# panel.net
KiCad netlist of a schematic drawn in EAGLE
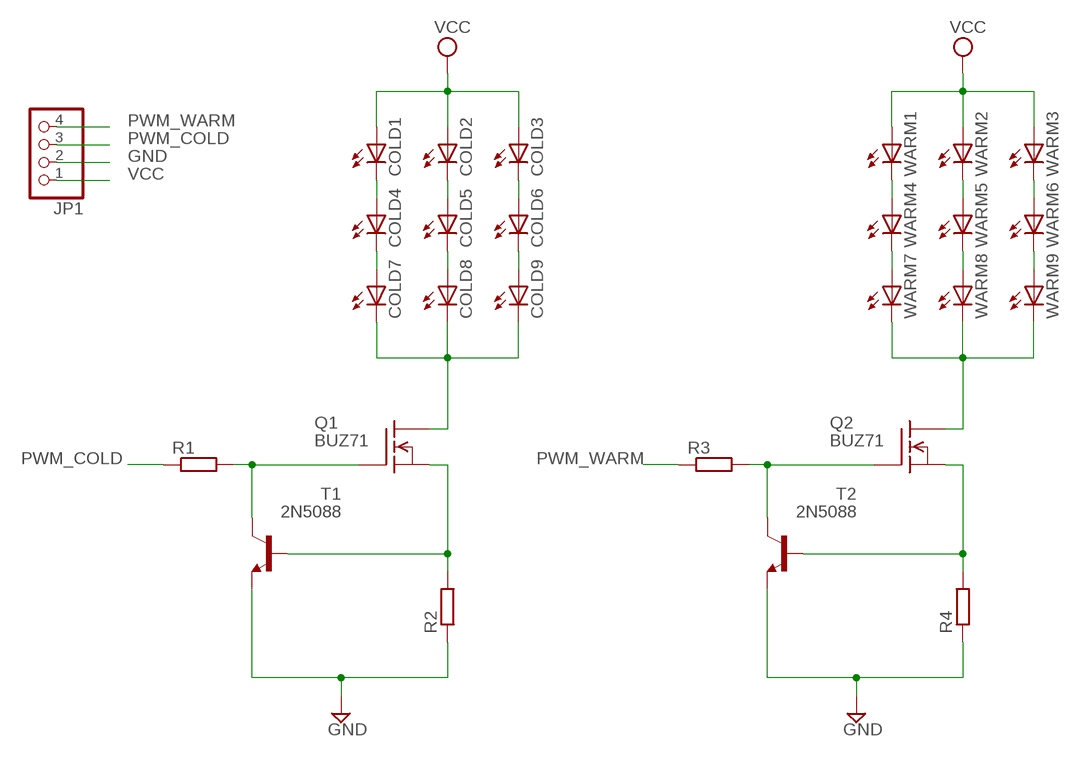
[diagram p0: schematic, sheet 1]

(export (version "E")
  (design (tool "Eeschema 10.0.6"))
  (components
    (comp (ref "COLD1")
      (value "LEDP-LCC-2")
      (footprint "eagle-import:P-LCC-2")
      (libsource (lib "eagle-import") (part "LEDP-LCC-2"))
    )
    (comp (ref "COLD2")
      (value "LEDP-LCC-2")
      (footprint "eagle-import:P-LCC-2")
      (libsource (lib "eagle-import") (part "LEDP-LCC-2"))
    )
    (comp (ref "COLD3")
      (value "LEDP-LCC-2")
      (footprint "eagle-import:P-LCC-2")
      (libsource (lib "eagle-import") (part "LEDP-LCC-2"))
    )
    (comp (ref "COLD4")
      (value "LEDP-LCC-2")
      (footprint "eagle-import:P-LCC-2")
      (libsource (lib "eagle-import") (part "LEDP-LCC-2"))
    )
    (comp (ref "COLD5")
      (value "LEDP-LCC-2")
      (footprint "eagle-import:P-LCC-2")
      (libsource (lib "eagle-import") (part "LEDP-LCC-2"))
    )
    (comp (ref "COLD6")
      (value "LEDP-LCC-2")
      (footprint "eagle-import:P-LCC-2")
      (libsource (lib "eagle-import") (part "LEDP-LCC-2"))
    )
    (comp (ref "COLD7")
      (value "LEDP-LCC-2")
      (footprint "eagle-import:P-LCC-2")
      (libsource (lib "eagle-import") (part "LEDP-LCC-2"))
    )
    (comp (ref "COLD8")
      (value "LEDP-LCC-2")
      (footprint "eagle-import:P-LCC-2")
      (libsource (lib "eagle-import") (part "LEDP-LCC-2"))
    )
    (comp (ref "COLD9")
      (value "LEDP-LCC-2")
      (footprint "eagle-import:P-LCC-2")
      (libsource (lib "eagle-import") (part "LEDP-LCC-2"))
    )
    (comp (ref "JP1")
      (value "PINHD-1X4")
      (footprint "eagle-import:1X04")
      (libsource (lib "eagle-import") (part "PINHD-1X4"))
    )
    (comp (ref "Q1")
      (value "BUZ71")
      (footprint "eagle-import:TO220")
      (libsource (lib "eagle-import") (part "BUZ71"))
    )
    (comp (ref "Q2")
      (value "BUZ71")
      (footprint "eagle-import:TO220")
      (libsource (lib "eagle-import") (part "BUZ71"))
    )
    (comp (ref "R1")
      (value "R-EU_0207/10")
      (footprint "eagle-import:0207_10")
      (libsource (lib "eagle-import") (part "R-EU_0207/10"))
    )
    (comp (ref "R2")
      (value "R-EU_0207/10")
      (footprint "eagle-import:0207_10")
      (libsource (lib "eagle-import") (part "R-EU_0207/10"))
    )
    (comp (ref "R3")
      (value "R-EU_0207/10")
      (footprint "eagle-import:0207_10")
      (libsource (lib "eagle-import") (part "R-EU_0207/10"))
    )
    (comp (ref "R4")
      (value "R-EU_0207/10")
      (footprint "eagle-import:0207_10")
      (libsource (lib "eagle-import") (part "R-EU_0207/10"))
    )
    (comp (ref "T1")
      (value "2N5088")
      (footprint "eagle-import:TO92")
      (libsource (lib "eagle-import") (part "2N5088"))
    )
    (comp (ref "T2")
      (value "2N5088")
      (footprint "eagle-import:TO92")
      (libsource (lib "eagle-import") (part "2N5088"))
    )
    (comp (ref "WARM1")
      (value "LEDP-LCC-2")
      (footprint "eagle-import:P-LCC-2")
      (libsource (lib "eagle-import") (part "LEDP-LCC-2"))
    )
    (comp (ref "WARM2")
      (value "LEDP-LCC-2")
      (footprint "eagle-import:P-LCC-2")
      (libsource (lib "eagle-import") (part "LEDP-LCC-2"))
    )
    (comp (ref "WARM3")
      (value "LEDP-LCC-2")
      (footprint "eagle-import:P-LCC-2")
      (libsource (lib "eagle-import") (part "LEDP-LCC-2"))
    )
    (comp (ref "WARM4")
      (value "LEDP-LCC-2")
      (footprint "eagle-import:P-LCC-2")
      (libsource (lib "eagle-import") (part "LEDP-LCC-2"))
    )
    (comp (ref "WARM5")
      (value "LEDP-LCC-2")
      (footprint "eagle-import:P-LCC-2")
      (libsource (lib "eagle-import") (part "LEDP-LCC-2"))
    )
    (comp (ref "WARM6")
      (value "LEDP-LCC-2")
      (footprint "eagle-import:P-LCC-2")
      (libsource (lib "eagle-import") (part "LEDP-LCC-2"))
    )
    (comp (ref "WARM7")
      (value "LEDP-LCC-2")
      (footprint "eagle-import:P-LCC-2")
      (libsource (lib "eagle-import") (part "LEDP-LCC-2"))
    )
    (comp (ref "WARM8")
      (value "LEDP-LCC-2")
      (footprint "eagle-import:P-LCC-2")
      (libsource (lib "eagle-import") (part "LEDP-LCC-2"))
    )
    (comp (ref "WARM9")
      (value "LEDP-LCC-2")
      (footprint "eagle-import:P-LCC-2")
      (libsource (lib "eagle-import") (part "LEDP-LCC-2"))
    )
  )
  (nets
    (net (code "1") (name "/PWM_COLD") (class "Default")
      (node (ref "JP1") (pin "3") (pinfunction "3_3") (pintype "passive"))
      (node (ref "R1") (pin "1") (pinfunction "1_1") (pintype "passive"))
    )
    (net (code "2") (name "/PWM_WARM") (class "Default")
      (node (ref "JP1") (pin "4") (pinfunction "4_4") (pintype "passive"))
      (node (ref "R3") (pin "1") (pinfunction "1_1") (pintype "passive"))
    )
    (net (code "3") (name "GND") (class "Default")
      (node (ref "JP1") (pin "2") (pinfunction "2_2") (pintype "passive"))
      (node (ref "R2") (pin "1") (pinfunction "1_1") (pintype "passive"))
      (node (ref "R4") (pin "1") (pinfunction "1_1") (pintype "passive"))
      (node (ref "T1") (pin "3") (pinfunction "E_3") (pintype "passive"))
      (node (ref "T2") (pin "3") (pinfunction "E_3") (pintype "passive"))
    )
    (net (code "4") (name "Net-(COLD1-PadC)") (class "Default")
      (node (ref "COLD1") (pin "C") (pinfunction "C_C") (pintype "passive"))
      (node (ref "COLD4") (pin "A") (pinfunction "A_A") (pintype "passive"))
    )
    (net (code "5") (name "Net-(COLD2-PadC)") (class "Default")
      (node (ref "COLD2") (pin "C") (pinfunction "C_C") (pintype "passive"))
      (node (ref "COLD5") (pin "A") (pinfunction "A_A") (pintype "passive"))
    )
    (net (code "6") (name "Net-(COLD3-PadC)") (class "Default")
      (node (ref "COLD3") (pin "C") (pinfunction "C_C") (pintype "passive"))
      (node (ref "COLD6") (pin "A") (pinfunction "A_A") (pintype "passive"))
    )
    (net (code "7") (name "Net-(COLD4-PadC)") (class "Default")
      (node (ref "COLD4") (pin "C") (pinfunction "C_C") (pintype "passive"))
      (node (ref "COLD7") (pin "A") (pinfunction "A_A") (pintype "passive"))
    )
    (net (code "8") (name "Net-(COLD5-PadC)") (class "Default")
      (node (ref "COLD5") (pin "C") (pinfunction "C_C") (pintype "passive"))
      (node (ref "COLD8") (pin "A") (pinfunction "A_A") (pintype "passive"))
    )
    (net (code "9") (name "Net-(COLD6-PadC)") (class "Default")
      (node (ref "COLD6") (pin "C") (pinfunction "C_C") (pintype "passive"))
      (node (ref "COLD9") (pin "A") (pinfunction "A_A") (pintype "passive"))
    )
    (net (code "10") (name "Net-(Q1-D)") (class "Default")
      (node (ref "COLD7") (pin "C") (pinfunction "C_C") (pintype "passive"))
      (node (ref "COLD8") (pin "C") (pinfunction "C_C") (pintype "passive"))
      (node (ref "COLD9") (pin "C") (pinfunction "C_C") (pintype "passive"))
      (node (ref "Q1") (pin "2") (pinfunction "D_2") (pintype "passive"))
    )
    (net (code "11") (name "Net-(Q1-G)") (class "Default")
      (node (ref "Q1") (pin "1") (pinfunction "G_1") (pintype "passive"))
      (node (ref "R1") (pin "2") (pinfunction "2_2") (pintype "passive"))
      (node (ref "T1") (pin "1") (pinfunction "C_1") (pintype "passive"))
    )
    (net (code "12") (name "Net-(Q1-S)") (class "Default")
      (node (ref "Q1") (pin "3") (pinfunction "S_3") (pintype "passive"))
      (node (ref "R2") (pin "2") (pinfunction "2_2") (pintype "passive"))
      (node (ref "T1") (pin "2") (pinfunction "B_2") (pintype "passive"))
    )
    (net (code "13") (name "Net-(Q2-D)") (class "Default")
      (node (ref "Q2") (pin "2") (pinfunction "D_2") (pintype "passive"))
      (node (ref "WARM7") (pin "C") (pinfunction "C_C") (pintype "passive"))
      (node (ref "WARM8") (pin "C") (pinfunction "C_C") (pintype "passive"))
      (node (ref "WARM9") (pin "C") (pinfunction "C_C") (pintype "passive"))
    )
    (net (code "14") (name "Net-(Q2-G)") (class "Default")
      (node (ref "Q2") (pin "1") (pinfunction "G_1") (pintype "passive"))
      (node (ref "R3") (pin "2") (pinfunction "2_2") (pintype "passive"))
      (node (ref "T2") (pin "1") (pinfunction "C_1") (pintype "passive"))
    )
    (net (code "15") (name "Net-(Q2-S)") (class "Default")
      (node (ref "Q2") (pin "3") (pinfunction "S_3") (pintype "passive"))
      (node (ref "R4") (pin "2") (pinfunction "2_2") (pintype "passive"))
      (node (ref "T2") (pin "2") (pinfunction "B_2") (pintype "passive"))
    )
    (net (code "16") (name "Net-(WARM1-PadC)") (class "Default")
      (node (ref "WARM1") (pin "C") (pinfunction "C_C") (pintype "passive"))
      (node (ref "WARM4") (pin "A") (pinfunction "A_A") (pintype "passive"))
    )
    (net (code "17") (name "Net-(WARM2-PadC)") (class "Default")
      (node (ref "WARM2") (pin "C") (pinfunction "C_C") (pintype "passive"))
      (node (ref "WARM5") (pin "A") (pinfunction "A_A") (pintype "passive"))
    )
    (net (code "18") (name "Net-(WARM3-PadC)") (class "Default")
      (node (ref "WARM3") (pin "C") (pinfunction "C_C") (pintype "passive"))
      (node (ref "WARM6") (pin "A") (pinfunction "A_A") (pintype "passive"))
    )
    (net (code "19") (name "Net-(WARM4-PadC)") (class "Default")
      (node (ref "WARM4") (pin "C") (pinfunction "C_C") (pintype "passive"))
      (node (ref "WARM7") (pin "A") (pinfunction "A_A") (pintype "passive"))
    )
    (net (code "20") (name "Net-(WARM5-PadC)") (class "Default")
      (node (ref "WARM5") (pin "C") (pinfunction "C_C") (pintype "passive"))
      (node (ref "WARM8") (pin "A") (pinfunction "A_A") (pintype "passive"))
    )
    (net (code "21") (name "Net-(WARM6-PadC)") (class "Default")
      (node (ref "WARM6") (pin "C") (pinfunction "C_C") (pintype "passive"))
      (node (ref "WARM9") (pin "A") (pinfunction "A_A") (pintype "passive"))
    )
    (net (code "22") (name "VCC") (class "Default")
      (node (ref "COLD1") (pin "A") (pinfunction "A_A") (pintype "passive"))
      (node (ref "COLD2") (pin "A") (pinfunction "A_A") (pintype "passive"))
      (node (ref "COLD3") (pin "A") (pinfunction "A_A") (pintype "passive"))
      (node (ref "JP1") (pin "1") (pinfunction "1_1") (pintype "passive"))
      (node (ref "WARM1") (pin "A") (pinfunction "A_A") (pintype "passive"))
      (node (ref "WARM2") (pin "A") (pinfunction "A_A") (pintype "passive"))
      (node (ref "WARM3") (pin "A") (pinfunction "A_A") (pintype "passive"))
    )
  )
)
